# platform_driver_all1.net
KiCad netlist of a schematic drawn in EAGLE
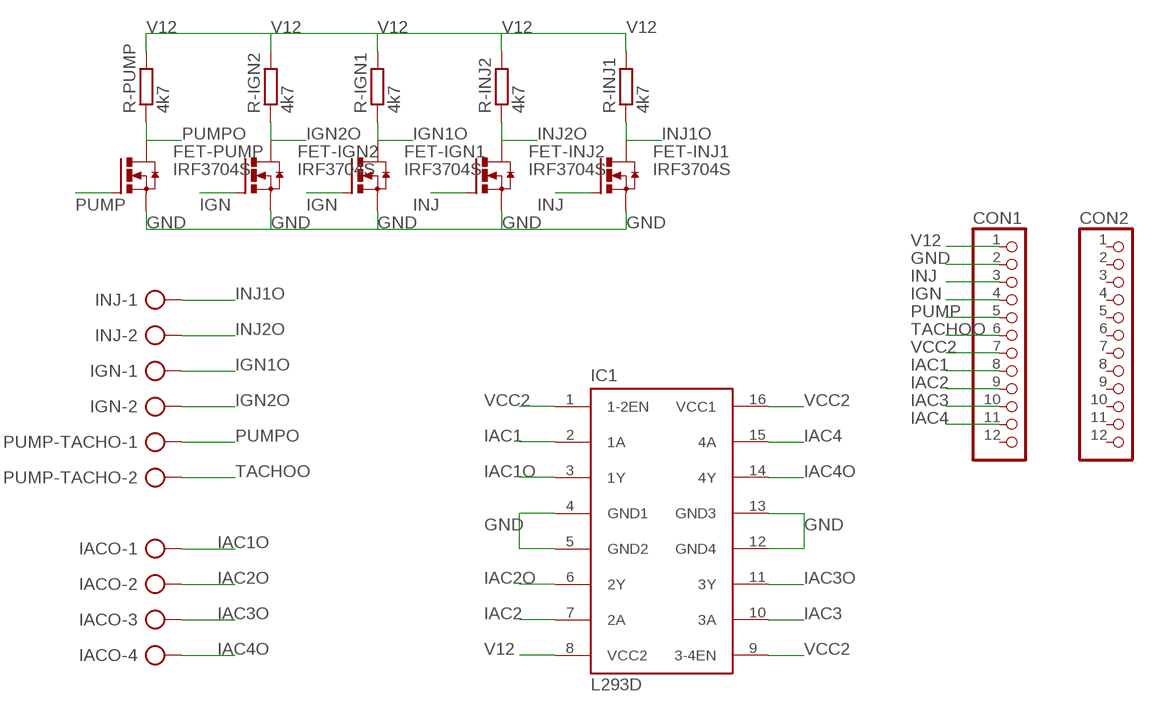
[diagram p0: schematic, sheet 1]

(export (version "E")
  (design (tool "Eeschema 10.0.6"))
  (components
    (comp (ref "CON1")
      (value "PINHD-1X12")
      (footprint "eagle-import:1X12")
      (libsource (lib "eagle-import") (part "PINHD-1X12"))
    )
    (comp (ref "CON2")
      (value "PINHD-1X12")
      (footprint "eagle-import:1X12")
      (libsource (lib "eagle-import") (part "PINHD-1X12"))
    )
    (comp (ref "FET-IGN1")
      (value "IRF3704S")
      (footprint "eagle-import:D2PACK")
      (libsource (lib "eagle-import") (part "IRF3704S"))
    )
    (comp (ref "FET-IGN2")
      (value "IRF3704S")
      (footprint "eagle-import:D2PACK")
      (libsource (lib "eagle-import") (part "IRF3704S"))
    )
    (comp (ref "FET-INJ1")
      (value "IRF3704S")
      (footprint "eagle-import:D2PACK")
      (libsource (lib "eagle-import") (part "IRF3704S"))
    )
    (comp (ref "FET-INJ2")
      (value "IRF3704S")
      (footprint "eagle-import:D2PACK")
      (libsource (lib "eagle-import") (part "IRF3704S"))
    )
    (comp (ref "FET-PUMP")
      (value "IRF3704S")
      (footprint "eagle-import:D2PACK")
      (libsource (lib "eagle-import") (part "IRF3704S"))
    )
    (comp (ref "IACO")
      (value "AK300/4")
      (footprint "eagle-import:AK300_4")
      (libsource (lib "eagle-import") (part "AK300/4"))
    )
    (comp (ref "IC1")
      (value "L293D")
      (footprint "eagle-import:DIL16")
      (libsource (lib "eagle-import") (part "L293D"))
    )
    (comp (ref "IGN")
      (value "AK300/2")
      (footprint "eagle-import:AK300_2")
      (libsource (lib "eagle-import") (part "AK300/2"))
    )
    (comp (ref "INJ")
      (value "AK300/2")
      (footprint "eagle-import:AK300_2")
      (libsource (lib "eagle-import") (part "AK300/2"))
    )
    (comp (ref "PUMP-TACHO")
      (value "AK300/2")
      (footprint "eagle-import:AK300_2")
      (libsource (lib "eagle-import") (part "AK300/2"))
    )
    (comp (ref "R-IGN1")
      (value "4k7")
      (footprint "eagle-import:M1206")
      (libsource (lib "eagle-import") (part "R-EU_M1206"))
    )
    (comp (ref "R-IGN2")
      (value "4k7")
      (footprint "eagle-import:M1206")
      (libsource (lib "eagle-import") (part "R-EU_M1206"))
    )
    (comp (ref "R-INJ1")
      (value "4k7")
      (footprint "eagle-import:M1206")
      (libsource (lib "eagle-import") (part "R-EU_M1206"))
    )
    (comp (ref "R-INJ2")
      (value "4k7")
      (footprint "eagle-import:M1206")
      (libsource (lib "eagle-import") (part "R-EU_M1206"))
    )
    (comp (ref "R-PUMP")
      (value "4k7")
      (footprint "eagle-import:M1206")
      (libsource (lib "eagle-import") (part "R-EU_M1206"))
    )
  )
  (nets
    (net (code "1") (name "/GND") (class "Default")
      (node (ref "CON1") (pin "2") (pinfunction "2_2") (pintype "passive"))
      (node (ref "FET-IGN1") (pin "3") (pinfunction "S_3") (pintype "passive"))
      (node (ref "FET-IGN2") (pin "3") (pinfunction "S_3") (pintype "passive"))
      (node (ref "FET-INJ1") (pin "3") (pinfunction "S_3") (pintype "passive"))
      (node (ref "FET-INJ2") (pin "3") (pinfunction "S_3") (pintype "passive"))
      (node (ref "FET-PUMP") (pin "3") (pinfunction "S_3") (pintype "passive"))
      (node (ref "IC1") (pin "12") (pinfunction "GND4_12") (pintype "power_in"))
      (node (ref "IC1") (pin "13") (pinfunction "GND3_13") (pintype "power_in"))
      (node (ref "IC1") (pin "4") (pinfunction "GND1_4") (pintype "power_in"))
      (node (ref "IC1") (pin "5") (pinfunction "GND2_5") (pintype "power_in"))
    )
    (net (code "2") (name "/IAC1") (class "Default")
      (node (ref "CON1") (pin "8") (pinfunction "8_8") (pintype "passive"))
      (node (ref "IC1") (pin "2") (pinfunction "1A_2") (pintype "input"))
    )
    (net (code "3") (name "/IAC1O") (class "Default")
      (node (ref "IACO") (pin "1") (pinfunction "KL_1") (pintype "passive"))
      (node (ref "IC1") (pin "3") (pinfunction "1Y_3") (pintype "output"))
    )
    (net (code "4") (name "/IAC2") (class "Default")
      (node (ref "CON1") (pin "9") (pinfunction "9_9") (pintype "passive"))
      (node (ref "IC1") (pin "7") (pinfunction "2A_7") (pintype "input"))
    )
    (net (code "5") (name "/IAC2O") (class "Default")
      (node (ref "IACO") (pin "2") (pinfunction "KL_2") (pintype "passive"))
      (node (ref "IC1") (pin "6") (pinfunction "2Y_6") (pintype "output"))
    )
    (net (code "6") (name "/IAC3") (class "Default")
      (node (ref "CON1") (pin "10") (pinfunction "10_10") (pintype "passive"))
      (node (ref "IC1") (pin "10") (pinfunction "3A_10") (pintype "input"))
    )
    (net (code "7") (name "/IAC3O") (class "Default")
      (node (ref "IACO") (pin "3") (pinfunction "KL_3") (pintype "passive"))
      (node (ref "IC1") (pin "11") (pinfunction "3Y_11") (pintype "output"))
    )
    (net (code "8") (name "/IAC4") (class "Default")
      (node (ref "CON1") (pin "11") (pinfunction "11_11") (pintype "passive"))
      (node (ref "IC1") (pin "15") (pinfunction "4A_15") (pintype "input"))
    )
    (net (code "9") (name "/IAC4O") (class "Default")
      (node (ref "IACO") (pin "4") (pinfunction "KL_4") (pintype "passive"))
      (node (ref "IC1") (pin "14") (pinfunction "4Y_14") (pintype "output"))
    )
    (net (code "10") (name "/IGN") (class "Default")
      (node (ref "CON1") (pin "4") (pinfunction "4_4") (pintype "passive"))
      (node (ref "FET-IGN1") (pin "1") (pinfunction "G_1") (pintype "passive"))
      (node (ref "FET-IGN2") (pin "1") (pinfunction "G_1") (pintype "passive"))
    )
    (net (code "11") (name "/IGN1O") (class "Default")
      (node (ref "FET-IGN1") (pin "2") (pinfunction "D_2") (pintype "passive"))
      (node (ref "IGN") (pin "1") (pinfunction "KL_1") (pintype "passive"))
      (node (ref "R-IGN1") (pin "1") (pinfunction "1_1") (pintype "passive"))
    )
    (net (code "12") (name "/IGN2O") (class "Default")
      (node (ref "FET-IGN2") (pin "2") (pinfunction "D_2") (pintype "passive"))
      (node (ref "IGN") (pin "2") (pinfunction "KL_2") (pintype "passive"))
      (node (ref "R-IGN2") (pin "1") (pinfunction "1_1") (pintype "passive"))
    )
    (net (code "13") (name "/INJ") (class "Default")
      (node (ref "CON1") (pin "3") (pinfunction "3_3") (pintype "passive"))
      (node (ref "FET-INJ1") (pin "1") (pinfunction "G_1") (pintype "passive"))
      (node (ref "FET-INJ2") (pin "1") (pinfunction "G_1") (pintype "passive"))
    )
    (net (code "14") (name "/INJ1O") (class "Default")
      (node (ref "FET-INJ1") (pin "2") (pinfunction "D_2") (pintype "passive"))
      (node (ref "INJ") (pin "1") (pinfunction "KL_1") (pintype "passive"))
      (node (ref "R-INJ1") (pin "1") (pinfunction "1_1") (pintype "passive"))
    )
    (net (code "15") (name "/INJ2O") (class "Default")
      (node (ref "FET-INJ2") (pin "2") (pinfunction "D_2") (pintype "passive"))
      (node (ref "INJ") (pin "2") (pinfunction "KL_2") (pintype "passive"))
      (node (ref "R-INJ2") (pin "1") (pinfunction "1_1") (pintype "passive"))
    )
    (net (code "16") (name "/PUMP") (class "Default")
      (node (ref "CON1") (pin "5") (pinfunction "5_5") (pintype "passive"))
      (node (ref "FET-PUMP") (pin "1") (pinfunction "G_1") (pintype "passive"))
    )
    (net (code "17") (name "/PUMPO") (class "Default")
      (node (ref "FET-PUMP") (pin "2") (pinfunction "D_2") (pintype "passive"))
      (node (ref "PUMP-TACHO") (pin "1") (pinfunction "KL_1") (pintype "passive"))
      (node (ref "R-PUMP") (pin "1") (pinfunction "1_1") (pintype "passive"))
    )
    (net (code "18") (name "/TACHOO") (class "Default")
      (node (ref "CON1") (pin "6") (pinfunction "6_6") (pintype "passive"))
      (node (ref "PUMP-TACHO") (pin "2") (pinfunction "KL_2") (pintype "passive"))
    )
    (net (code "19") (name "/V12") (class "Default")
      (node (ref "CON1") (pin "1") (pinfunction "1_1") (pintype "passive"))
      (node (ref "IC1") (pin "8") (pinfunction "VCC2_8") (pintype "power_in"))
      (node (ref "R-IGN1") (pin "2") (pinfunction "2_2") (pintype "passive"))
      (node (ref "R-IGN2") (pin "2") (pinfunction "2_2") (pintype "passive"))
      (node (ref "R-INJ1") (pin "2") (pinfunction "2_2") (pintype "passive"))
      (node (ref "R-INJ2") (pin "2") (pinfunction "2_2") (pintype "passive"))
      (node (ref "R-PUMP") (pin "2") (pinfunction "2_2") (pintype "passive"))
    )
    (net (code "20") (name "/VCC2") (class "Default")
      (node (ref "CON1") (pin "7") (pinfunction "7_7") (pintype "passive"))
      (node (ref "IC1") (pin "1") (pinfunction "1-2EN_1") (pintype "input"))
      (node (ref "IC1") (pin "16") (pinfunction "VCC1_16") (pintype "power_in"))
      (node (ref "IC1") (pin "9") (pinfunction "3-4EN_9") (pintype "input"))
    )
    (net (code "21") (name "unconnected-(CON1-Pad12)") (class "Default")
      (node (ref "CON1") (pin "12") (pinfunction "12_12") (pintype "passive"))
    )
    (net (code "22") (name "unconnected-(CON2-Pad1)") (class "Default")
      (node (ref "CON2") (pin "1") (pinfunction "1_1") (pintype "passive"))
    )
    (net (code "23") (name "unconnected-(CON2-Pad2)") (class "Default")
      (node (ref "CON2") (pin "2") (pinfunction "2_2") (pintype "passive"))
    )
    (net (code "24") (name "unconnected-(CON2-Pad3)") (class "Default")
      (node (ref "CON2") (pin "3") (pinfunction "3_3") (pintype "passive"))
    )
    (net (code "25") (name "unconnected-(CON2-Pad4)") (class "Default")
      (node (ref "CON2") (pin "4") (pinfunction "4_4") (pintype "passive"))
    )
    (net (code "26") (name "unconnected-(CON2-Pad5)") (class "Default")
      (node (ref "CON2") (pin "5") (pinfunction "5_5") (pintype "passive"))
    )
    (net (code "27") (name "unconnected-(CON2-Pad6)") (class "Default")
      (node (ref "CON2") (pin "6") (pinfunction "6_6") (pintype "passive"))
    )
    (net (code "28") (name "unconnected-(CON2-Pad7)") (class "Default")
      (node (ref "CON2") (pin "7") (pinfunction "7_7") (pintype "passive"))
    )
    (net (code "29") (name "unconnected-(CON2-Pad8)") (class "Default")
      (node (ref "CON2") (pin "8") (pinfunction "8_8") (pintype "passive"))
    )
    (net (code "30") (name "unconnected-(CON2-Pad9)") (class "Default")
      (node (ref "CON2") (pin "9") (pinfunction "9_9") (pintype "passive"))
    )
    (net (code "31") (name "unconnected-(CON2-Pad10)") (class "Default")
      (node (ref "CON2") (pin "10") (pinfunction "10_10") (pintype "passive"))
    )
    (net (code "32") (name "unconnected-(CON2-Pad11)") (class "Default")
      (node (ref "CON2") (pin "11") (pinfunction "11_11") (pintype "passive"))
    )
    (net (code "33") (name "unconnected-(CON2-Pad12)") (class "Default")
      (node (ref "CON2") (pin "12") (pinfunction "12_12") (pintype "passive"))
    )
  )
)
